# ss.net
KiCad netlist of a schematic drawn in EAGLE
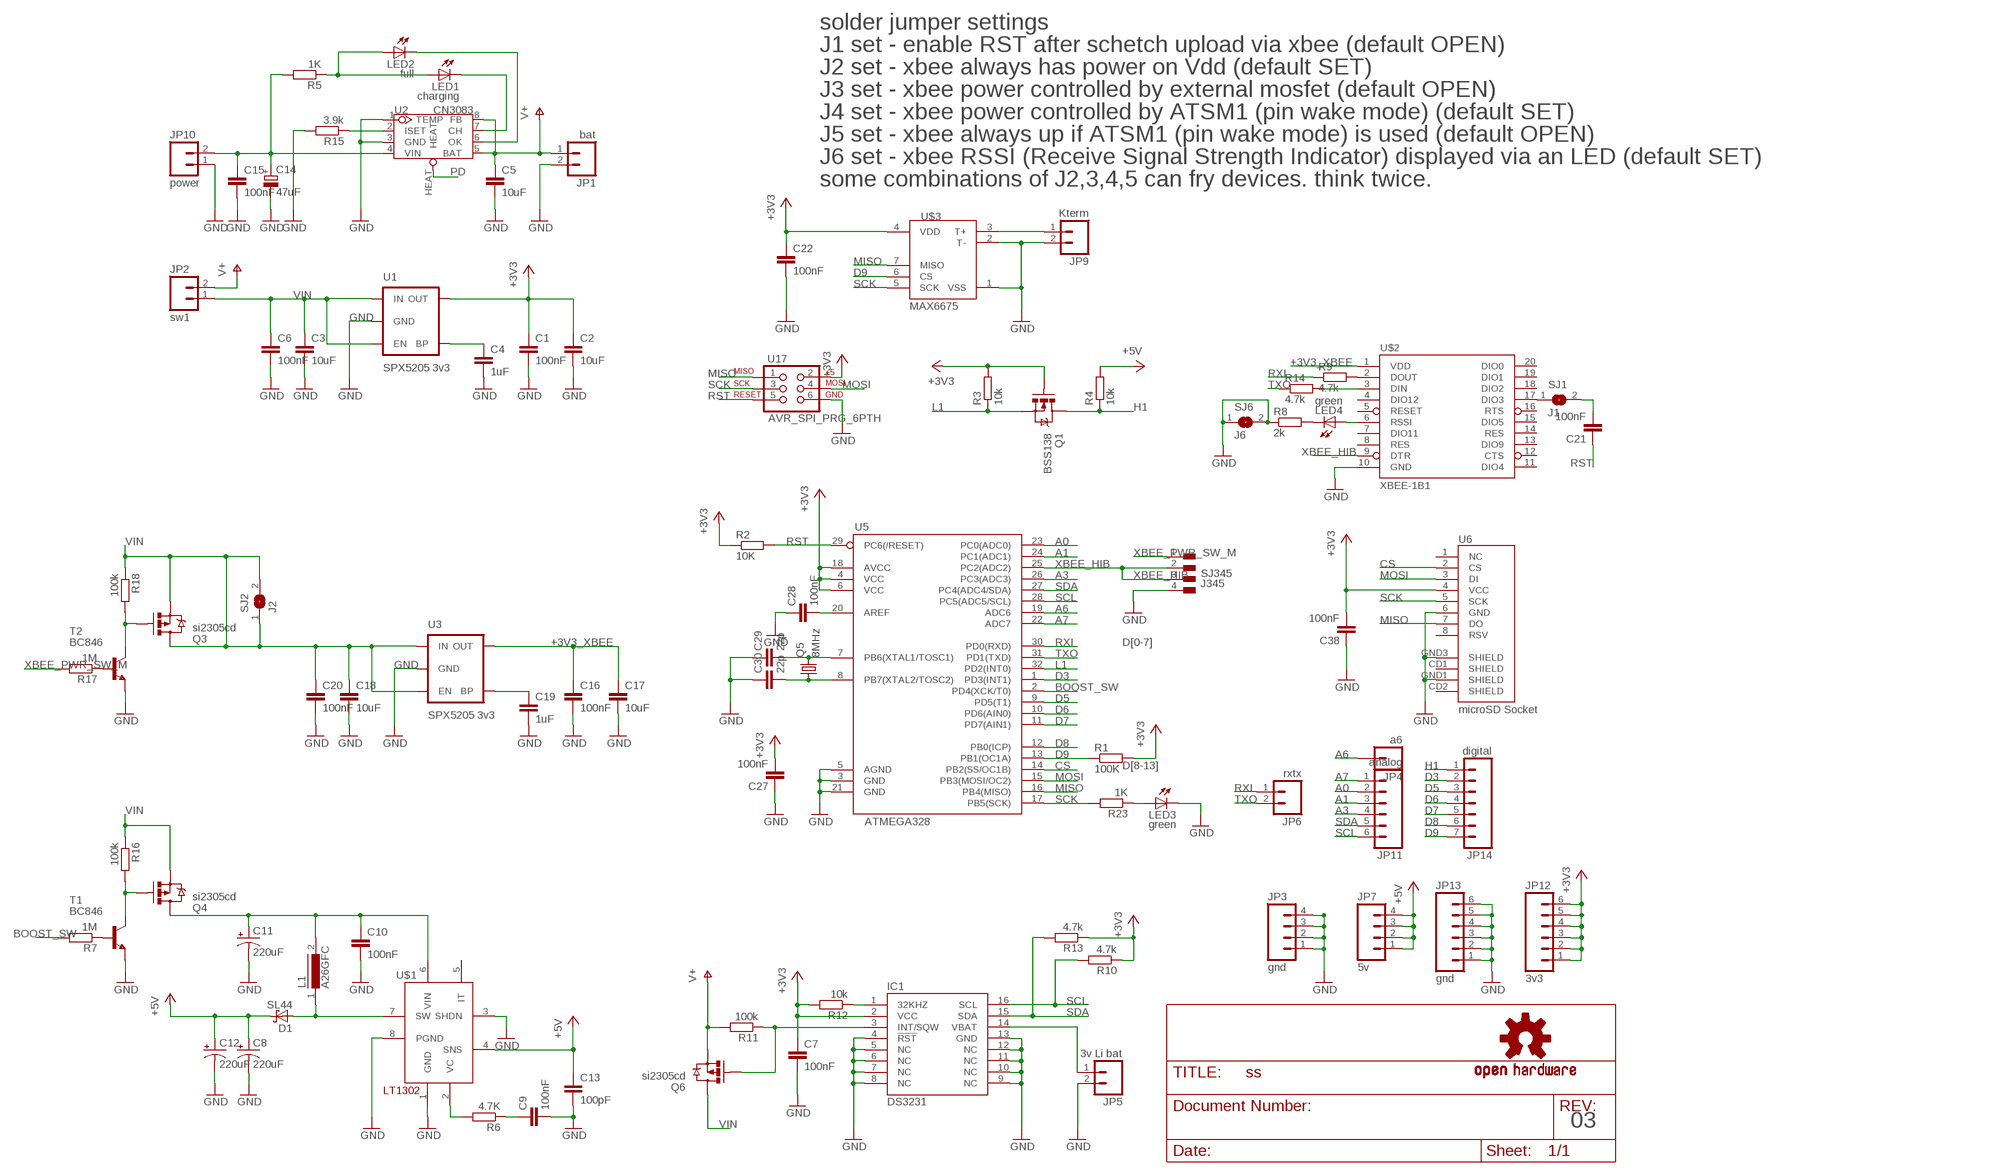
[diagram p0: schematic, sheet 1]

(export (version "E")
  (design (tool "Eeschema 10.0.6"))
  (components
    (comp (ref "C1")
      (value "100nF")
      (footprint "eagle-import:C0805")
      (libsource (lib "eagle-import") (part "C-EUC0805"))
    )
    (comp (ref "C2")
      (value "10uF")
      (footprint "eagle-import:C1206")
      (libsource (lib "eagle-import") (part "C-EUC1206"))
    )
    (comp (ref "C3")
      (value "10uF")
      (footprint "eagle-import:C1206")
      (libsource (lib "eagle-import") (part "C-EUC1206"))
    )
    (comp (ref "C4")
      (value "1uF")
      (footprint "eagle-import:C0805")
      (libsource (lib "eagle-import") (part "C-EUC0805"))
    )
    (comp (ref "C5")
      (value "10uF")
      (footprint "eagle-import:C1206")
      (libsource (lib "eagle-import") (part "C-EUC1206"))
    )
    (comp (ref "C6")
      (value "100nF")
      (footprint "eagle-import:C0805")
      (libsource (lib "eagle-import") (part "C-EUC0805"))
    )
    (comp (ref "C7")
      (value "100nF")
      (footprint "eagle-import:C0805")
      (libsource (lib "eagle-import") (part "C-EUC0805"))
    )
    (comp (ref "C8")
      (value "220uF")
      (footprint "eagle-import:PANASONIC_D")
      (libsource (lib "eagle-import") (part "CAP_POLD"))
    )
    (comp (ref "C9")
      (value "100nF")
      (footprint "eagle-import:C0805")
      (libsource (lib "eagle-import") (part "C-EUC0805"))
    )
    (comp (ref "C10")
      (value "100nF")
      (footprint "eagle-import:C0805")
      (libsource (lib "eagle-import") (part "C-EUC0805"))
    )
    (comp (ref "C11")
      (value "220uF")
      (footprint "eagle-import:PANASONIC_D")
      (libsource (lib "eagle-import") (part "CAP_POLD"))
    )
    (comp (ref "C12")
      (value "220uF")
      (footprint "eagle-import:PANASONIC_D")
      (libsource (lib "eagle-import") (part "CAP_POLD"))
    )
    (comp (ref "C13")
      (value "100pF")
      (footprint "eagle-import:C0805")
      (libsource (lib "eagle-import") (part "C-EUC0805"))
    )
    (comp (ref "C14")
      (value "47uF")
      (footprint "eagle-import:CT7343")
      (libsource (lib "eagle-import") (part "CPOL-EUCT7343"))
    )
    (comp (ref "C15")
      (value "100nF")
      (footprint "eagle-import:C0805")
      (libsource (lib "eagle-import") (part "C-EUC0805"))
    )
    (comp (ref "C16")
      (value "100nF")
      (footprint "eagle-import:C0805")
      (libsource (lib "eagle-import") (part "C-EUC0805"))
    )
    (comp (ref "C17")
      (value "10uF")
      (footprint "eagle-import:C1206")
      (libsource (lib "eagle-import") (part "C-EUC1206"))
    )
    (comp (ref "C18")
      (value "10uF")
      (footprint "eagle-import:C1206")
      (libsource (lib "eagle-import") (part "C-EUC1206"))
    )
    (comp (ref "C19")
      (value "1uF")
      (footprint "eagle-import:C0805")
      (libsource (lib "eagle-import") (part "C-EUC0805"))
    )
    (comp (ref "C20")
      (value "100nF")
      (footprint "eagle-import:C0805")
      (libsource (lib "eagle-import") (part "C-EUC0805"))
    )
    (comp (ref "C21")
      (value "100nF")
      (footprint "eagle-import:C0805")
      (libsource (lib "eagle-import") (part "C-EUC0805"))
    )
    (comp (ref "C22")
      (value "100nF")
      (footprint "eagle-import:C0805")
      (libsource (lib "eagle-import") (part "C-EUC0805"))
    )
    (comp (ref "C27")
      (value "100nF")
      (footprint "eagle-import:C0805")
      (libsource (lib "eagle-import") (part "C-EUC0805"))
    )
    (comp (ref "C28")
      (value "100nF")
      (footprint "eagle-import:C0805")
      (libsource (lib "eagle-import") (part "C-EUC0805"))
    )
    (comp (ref "C29")
      (value "22p")
      (footprint "eagle-import:C0805")
      (libsource (lib "eagle-import") (part "C-EUC0805"))
    )
    (comp (ref "C30")
      (value "22p")
      (footprint "eagle-import:C0805")
      (libsource (lib "eagle-import") (part "C-EUC0805"))
    )
    (comp (ref "C38")
      (value "100nF")
      (footprint "eagle-import:C0805")
      (libsource (lib "eagle-import") (part "C-EUC0805"))
    )
    (comp (ref "D1")
      (value "SL44")
      (footprint "eagle-import:SMC")
      (libsource (lib "eagle-import") (part "SCHOTTKY-DIODESMC"))
    )
    (comp (ref "IC1")
      (value "DS3231")
      (footprint "eagle-import:SO-16")
      (libsource (lib "eagle-import") (part "DS3231"))
    )
    (comp (ref "JP1")
      (value "bat")
      (footprint "eagle-import:1X02")
      (libsource (lib "eagle-import") (part "M02PTH"))
    )
    (comp (ref "JP2")
      (value "sw1")
      (footprint "eagle-import:1X02")
      (libsource (lib "eagle-import") (part "M02PTH"))
    )
    (comp (ref "JP3")
      (value "gnd")
      (footprint "eagle-import:1X04")
      (libsource (lib "eagle-import") (part "M04PTH"))
    )
    (comp (ref "JP4")
      (value "a6")
      (footprint "eagle-import:1X01")
      (libsource (lib "eagle-import") (part "M01PTH"))
    )
    (comp (ref "JP5")
      (value "3v Li bat")
      (footprint "eagle-import:1X02")
      (libsource (lib "eagle-import") (part "M02PTH"))
    )
    (comp (ref "JP6")
      (value "rxtx")
      (footprint "eagle-import:1X02")
      (libsource (lib "eagle-import") (part "M02PTH"))
    )
    (comp (ref "JP7")
      (value "5v")
      (footprint "eagle-import:1X04")
      (libsource (lib "eagle-import") (part "M04PTH"))
    )
    (comp (ref "JP9")
      (value "Kterm")
      (footprint "eagle-import:1X02")
      (libsource (lib "eagle-import") (part "M02PTH"))
    )
    (comp (ref "JP10")
      (value "power")
      (footprint "eagle-import:1X02")
      (libsource (lib "eagle-import") (part "M02PTH"))
    )
    (comp (ref "JP11")
      (value "analog")
      (footprint "eagle-import:1X06")
      (libsource (lib "eagle-import") (part "M06SIP"))
    )
    (comp (ref "JP12")
      (value "3v3")
      (footprint "eagle-import:1X06")
      (libsource (lib "eagle-import") (part "M06SIP"))
    )
    (comp (ref "JP13")
      (value "gnd")
      (footprint "eagle-import:1X06")
      (libsource (lib "eagle-import") (part "M06SIP"))
    )
    (comp (ref "JP14")
      (value "digital")
      (footprint "eagle-import:1X07")
      (libsource (lib "eagle-import") (part "M07"))
    )
    (comp (ref "L1")
      (value "A26GFC")
      (footprint "eagle-import:A26GFC")
      (libsource (lib "eagle-import") (part "A26GFC"))
    )
    (comp (ref "LED1")
      (value "charging")
      (footprint "eagle-import:CHIP-LED0805")
      (libsource (lib "eagle-import") (part "LEDCHIP-LED0805"))
    )
    (comp (ref "LED2")
      (value "full")
      (footprint "eagle-import:CHIP-LED0805")
      (libsource (lib "eagle-import") (part "LEDCHIP-LED0805"))
    )
    (comp (ref "LED3")
      (value "green")
      (footprint "eagle-import:CHIP-LED0805")
      (libsource (lib "eagle-import") (part "LEDCHIP-LED0805"))
    )
    (comp (ref "LED4")
      (value "green")
      (footprint "eagle-import:CHIP-LED0805")
      (libsource (lib "eagle-import") (part "LEDCHIP-LED0805"))
    )
    (comp (ref "Q1")
      (value "BSS138")
      (footprint "eagle-import:SOT23-3")
      (libsource (lib "eagle-import") (part "MOSFET-NCHANNELSMD"))
    )
    (comp (ref "Q3")
      (value "si2305cd")
      (footprint "eagle-import:SOT23-3_POWER")
      (libsource (lib "eagle-import") (part "MOSFET-PCHANNELSMD_POWER"))
    )
    (comp (ref "Q4")
      (value "si2305cd")
      (footprint "eagle-import:SOT23-3_POWER")
      (libsource (lib "eagle-import") (part "MOSFET-PCHANNELSMD_POWER"))
    )
    (comp (ref "Q5")
      (value "8MHz")
      (footprint "eagle-import:CRYSTAL_5X3.2")
      (libsource (lib "eagle-import") (part "CRYTAL"))
    )
    (comp (ref "Q6")
      (value "si2305cd")
      (footprint "eagle-import:SOT23-3_POWER")
      (libsource (lib "eagle-import") (part "MOSFET-PCHANNELSMD_POWER"))
    )
    (comp (ref "R1")
      (value "100K")
      (footprint "eagle-import:R0805W")
      (libsource (lib "eagle-import") (part "R-EU_R0805W"))
    )
    (comp (ref "R2")
      (value "10K")
      (footprint "eagle-import:R0805W")
      (libsource (lib "eagle-import") (part "R-EU_R0805W"))
    )
    (comp (ref "R3")
      (value "10k")
      (footprint "eagle-import:R0805W")
      (libsource (lib "eagle-import") (part "R-EU_R0805W"))
    )
    (comp (ref "R4")
      (value "10k")
      (footprint "eagle-import:R0805W")
      (libsource (lib "eagle-import") (part "R-EU_R0805W"))
    )
    (comp (ref "R5")
      (value "1K")
      (footprint "eagle-import:R0805W")
      (libsource (lib "eagle-import") (part "R-EU_R0805W"))
    )
    (comp (ref "R6")
      (value "4.7K")
      (footprint "eagle-import:R0805W")
      (libsource (lib "eagle-import") (part "R-EU_R0805W"))
    )
    (comp (ref "R7")
      (value "1M")
      (footprint "eagle-import:R0805W")
      (libsource (lib "eagle-import") (part "R-EU_R0805W"))
    )
    (comp (ref "R8")
      (value "2k")
      (footprint "eagle-import:R0805W")
      (libsource (lib "eagle-import") (part "R-EU_R0805W"))
    )
    (comp (ref "R9")
      (value "4.7k")
      (footprint "eagle-import:R0805W")
      (libsource (lib "eagle-import") (part "R-EU_R0805W"))
    )
    (comp (ref "R10")
      (value "4.7k")
      (footprint "eagle-import:R0805W")
      (libsource (lib "eagle-import") (part "R-EU_R0805W"))
    )
    (comp (ref "R11")
      (value "100k")
      (footprint "eagle-import:R0805W")
      (libsource (lib "eagle-import") (part "R-EU_R0805W"))
    )
    (comp (ref "R12")
      (value "10k")
      (footprint "eagle-import:R0805W")
      (libsource (lib "eagle-import") (part "R-EU_R0805W"))
    )
    (comp (ref "R13")
      (value "4.7k")
      (footprint "eagle-import:R0805W")
      (libsource (lib "eagle-import") (part "R-EU_R0805W"))
    )
    (comp (ref "R14")
      (value "4.7k")
      (footprint "eagle-import:R0805W")
      (libsource (lib "eagle-import") (part "R-EU_R0805W"))
    )
    (comp (ref "R15")
      (value "3.9k")
      (footprint "eagle-import:R0805W")
      (libsource (lib "eagle-import") (part "R-EU_R0805W"))
    )
    (comp (ref "R16")
      (value "100k")
      (footprint "eagle-import:R0805W")
      (libsource (lib "eagle-import") (part "R-EU_R0805W"))
    )
    (comp (ref "R17")
      (value "1M")
      (footprint "eagle-import:R0805W")
      (libsource (lib "eagle-import") (part "R-EU_R0805W"))
    )
    (comp (ref "R18")
      (value "100k")
      (footprint "eagle-import:R0805W")
      (libsource (lib "eagle-import") (part "R-EU_R0805W"))
    )
    (comp (ref "R23")
      (value "1K")
      (footprint "eagle-import:R0805W")
      (libsource (lib "eagle-import") (part "R-EU_R0805W"))
    )
    (comp (ref "SJ1") (value "J1") (footprint "eagle-import:SJ") (libsource (lib "eagle-import") (part "SJ")))
    (comp (ref "SJ2") (value "J2") (footprint "eagle-import:SJ") (libsource (lib "eagle-import") (part "SJ")))
    (comp (ref "SJ6") (value "J6") (footprint "eagle-import:SJ") (libsource (lib "eagle-import") (part "SJ")))
    (comp (ref "SJ345")
      (value "J345")
      (footprint "eagle-import:SJ_4P")
      (libsource (lib "eagle-import") (part "SJ_4P"))
    )
    (comp (ref "T1")
      (value "BC846")
      (footprint "eagle-import:SOT23")
      (libsource (lib "eagle-import") (part "BC846"))
    )
    (comp (ref "T2")
      (value "BC846")
      (footprint "eagle-import:SOT23")
      (libsource (lib "eagle-import") (part "BC846"))
    )
    (comp (ref "U$1")
      (value "LT1302SOIC8")
      (footprint "eagle-import:SO08")
      (libsource (lib "eagle-import") (part "LT1302SOIC8"))
    )
    (comp (ref "U$2")
      (value "XBEE-1B1")
      (footprint "eagle-import:XBEE-1")
      (libsource (lib "eagle-import") (part "XBEE-1B1"))
    )
    (comp (ref "U$3")
      (value "MAX6675")
      (footprint "eagle-import:SO08-MAX6675")
      (libsource (lib "eagle-import") (part "MAX6675"))
    )
    (comp (ref "U$7")
      (value "OSHW-LOGOM")
      (footprint "eagle-import:OSHW-LOGO-M")
      (libsource (lib "eagle-import") (part "OSHW-LOGOM"))
    )
    (comp (ref "U1")
      (value "SPX5205 3v3")
      (footprint "eagle-import:SOT23-5")
      (libsource (lib "eagle-import") (part "V_REG_LDOSMD"))
    )
    (comp (ref "U2")
      (value "CN3083")
      (footprint "eagle-import:SOP8-W_-HEAT")
      (libsource (lib "eagle-import") (part "CN3083"))
    )
    (comp (ref "U3")
      (value "SPX5205 3v3")
      (footprint "eagle-import:SOT23-5")
      (libsource (lib "eagle-import") (part "V_REG_LDOSMD"))
    )
    (comp (ref "U5")
      (value "ATMEGA328")
      (footprint "eagle-import:TQFP32-08")
      (libsource (lib "eagle-import") (part "ATMEGA168"))
    )
    (comp (ref "U6")
      (value "microSD Socket")
      (footprint "eagle-import:MICRO-SD-SOCKET-PP")
      (libsource (lib "eagle-import") (part "USD-SOCKETNEW"))
    )
    (comp (ref "U17")
      (value "AVR_SPI_PRG_6PTH")
      (footprint "eagle-import:2X3")
      (libsource (lib "eagle-import") (part "AVR_SPI_PRG_6PTH"))
    )
  )
  (nets
    (net (code "1") (name "+3V3") (class "Default")
      (node (ref "C1") (pin "1") (pinfunction "1_1") (pintype "passive"))
      (node (ref "C2") (pin "1") (pinfunction "1_1") (pintype "passive"))
      (node (ref "C22") (pin "1") (pinfunction "1_1") (pintype "passive"))
      (node (ref "C27") (pin "2") (pinfunction "2_2") (pintype "passive"))
      (node (ref "C38") (pin "2") (pinfunction "2_2") (pintype "passive"))
      (node (ref "C7") (pin "1") (pinfunction "1_1") (pintype "passive"))
      (node (ref "IC1") (pin "2") (pinfunction "VCC_2") (pintype "power_in"))
      (node (ref "JP12") (pin "1") (pinfunction "1_1") (pintype "passive"))
      (node (ref "JP12") (pin "2") (pinfunction "2_2") (pintype "passive"))
      (node (ref "JP12") (pin "3") (pinfunction "3_3") (pintype "passive"))
      (node (ref "JP12") (pin "4") (pinfunction "4_4") (pintype "passive"))
      (node (ref "JP12") (pin "5") (pinfunction "5_5") (pintype "passive"))
      (node (ref "JP12") (pin "6") (pinfunction "6_6") (pintype "passive"))
      (node (ref "Q1") (pin "1") (pinfunction "G_1") (pintype "passive"))
      (node (ref "R1") (pin "2") (pinfunction "2_2") (pintype "passive"))
      (node (ref "R10") (pin "1") (pinfunction "1_1") (pintype "passive"))
      (node (ref "R12") (pin "2") (pinfunction "2_2") (pintype "passive"))
      (node (ref "R13") (pin "1") (pinfunction "1_1") (pintype "passive"))
      (node (ref "R2") (pin "1") (pinfunction "1_1") (pintype "passive"))
      (node (ref "R3") (pin "2") (pinfunction "2_2") (pintype "passive"))
      (node (ref "U$3") (pin "4") (pinfunction "VDD_4") (pintype "bidirectional"))
      (node (ref "U1") (pin "5") (pinfunction "OUT_5") (pintype "passive"))
      (node (ref "U17") (pin "2") (pinfunction "2_2") (pintype "passive"))
      (node (ref "U5") (pin "18") (pinfunction "AVCC_18") (pintype "bidirectional"))
      (node (ref "U5") (pin "4") (pinfunction "VCC_4") (pintype "bidirectional"))
      (node (ref "U5") (pin "6") (pinfunction "VCC_6") (pintype "bidirectional"))
      (node (ref "U6") (pin "4") (pinfunction "VCC_4") (pintype "bidirectional"))
    )
    (net (code "2") (name "+5V") (class "Default")
      (node (ref "C12") (pin "+") (pinfunction "+_+") (pintype "passive"))
      (node (ref "C13") (pin "1") (pinfunction "1_1") (pintype "passive"))
      (node (ref "C8") (pin "+") (pinfunction "+_+") (pintype "passive"))
      (node (ref "D1") (pin "C") (pinfunction "C_C") (pintype "passive"))
      (node (ref "JP7") (pin "1") (pinfunction "1_1") (pintype "passive"))
      (node (ref "JP7") (pin "2") (pinfunction "2_2") (pintype "passive"))
      (node (ref "JP7") (pin "3") (pinfunction "3_3") (pintype "passive"))
      (node (ref "JP7") (pin "4") (pinfunction "4_4") (pintype "passive"))
      (node (ref "R4") (pin "2") (pinfunction "2_2") (pintype "passive"))
      (node (ref "U$1") (pin "4") (pinfunction "SNS_4") (pintype "passive"))
    )
    (net (code "3") (name "/+3V3_XBEE") (class "Default")
      (node (ref "C16") (pin "1") (pinfunction "1_1") (pintype "passive"))
      (node (ref "C17") (pin "1") (pinfunction "1_1") (pintype "passive"))
      (node (ref "U$2") (pin "1") (pinfunction "VDD_1") (pintype "power_in"))
      (node (ref "U3") (pin "5") (pinfunction "OUT_5") (pintype "passive"))
    )
    (net (code "4") (name "/A0") (class "Default")
      (node (ref "JP11") (pin "2") (pinfunction "2_2") (pintype "passive"))
      (node (ref "U5") (pin "23") (pinfunction "PC0(ADC0)_23") (pintype "bidirectional"))
    )
    (net (code "5") (name "/A1") (class "Default")
      (node (ref "JP11") (pin "3") (pinfunction "3_3") (pintype "passive"))
      (node (ref "U5") (pin "24") (pinfunction "PC1(ADC1)_24") (pintype "bidirectional"))
    )
    (net (code "6") (name "/A3") (class "Default")
      (node (ref "JP11") (pin "4") (pinfunction "4_4") (pintype "passive"))
      (node (ref "U5") (pin "26") (pinfunction "PC3(ADC3)_26") (pintype "bidirectional"))
    )
    (net (code "7") (name "/A6") (class "Default")
      (node (ref "JP4") (pin "1") (pinfunction "1_1") (pintype "passive"))
      (node (ref "U5") (pin "19") (pinfunction "ADC6_19") (pintype "bidirectional"))
    )
    (net (code "8") (name "/A7") (class "Default")
      (node (ref "JP11") (pin "1") (pinfunction "1_1") (pintype "passive"))
      (node (ref "U5") (pin "22") (pinfunction "ADC7_22") (pintype "bidirectional"))
    )
    (net (code "9") (name "/BOOST_SW") (class "Default")
      (node (ref "R7") (pin "2") (pinfunction "2_2") (pintype "passive"))
      (node (ref "U5") (pin "2") (pinfunction "PD4(XCK/T0)_2") (pintype "bidirectional"))
    )
    (net (code "10") (name "/CS") (class "Default")
      (node (ref "U5") (pin "14") (pinfunction "PB2(SS/OC1B)_14") (pintype "bidirectional"))
      (node (ref "U6") (pin "2") (pinfunction "CS_2") (pintype "bidirectional"))
    )
    (net (code "11") (name "/D3") (class "Default")
      (node (ref "JP14") (pin "2") (pinfunction "2_2") (pintype "passive"))
      (node (ref "U5") (pin "1") (pinfunction "PD3(INT1)_1") (pintype "bidirectional"))
    )
    (net (code "12") (name "/D5") (class "Default")
      (node (ref "JP14") (pin "3") (pinfunction "3_3") (pintype "passive"))
      (node (ref "U5") (pin "9") (pinfunction "PD5(T1)_9") (pintype "bidirectional"))
    )
    (net (code "13") (name "/D6") (class "Default")
      (node (ref "JP14") (pin "4") (pinfunction "4_4") (pintype "passive"))
      (node (ref "U5") (pin "10") (pinfunction "PD6(AIN0)_10") (pintype "bidirectional"))
    )
    (net (code "14") (name "/D7") (class "Default")
      (node (ref "JP14") (pin "5") (pinfunction "5_5") (pintype "passive"))
      (node (ref "U5") (pin "11") (pinfunction "PD7(AIN1)_11") (pintype "bidirectional"))
    )
    (net (code "15") (name "/D8") (class "Default")
      (node (ref "JP14") (pin "6") (pinfunction "6_6") (pintype "passive"))
      (node (ref "U5") (pin "12") (pinfunction "PB0(ICP)_12") (pintype "bidirectional"))
    )
    (net (code "16") (name "/D9") (class "Default")
      (node (ref "JP14") (pin "7") (pinfunction "7_7") (pintype "passive"))
      (node (ref "R1") (pin "1") (pinfunction "1_1") (pintype "passive"))
      (node (ref "U$3") (pin "6") (pinfunction "CS_6") (pintype "bidirectional"))
      (node (ref "U5") (pin "13") (pinfunction "PB1(OC1A)_13") (pintype "bidirectional"))
    )
    (net (code "17") (name "/H1") (class "Default")
      (node (ref "JP14") (pin "1") (pinfunction "1_1") (pintype "passive"))
      (node (ref "Q1") (pin "3") (pinfunction "D_3") (pintype "passive"))
      (node (ref "R4") (pin "1") (pinfunction "1_1") (pintype "passive"))
    )
    (net (code "18") (name "/L1") (class "Default")
      (node (ref "Q1") (pin "2") (pinfunction "S_2") (pintype "passive"))
      (node (ref "R3") (pin "1") (pinfunction "1_1") (pintype "passive"))
      (node (ref "U5") (pin "32") (pinfunction "PD2(INT0)_32") (pintype "bidirectional"))
    )
    (net (code "19") (name "/MISO") (class "Default")
      (node (ref "U$3") (pin "7") (pinfunction "MISO_7") (pintype "bidirectional"))
      (node (ref "U17") (pin "1") (pinfunction "1_1") (pintype "passive"))
      (node (ref "U5") (pin "16") (pinfunction "PB4(MISO)_16") (pintype "bidirectional"))
      (node (ref "U6") (pin "7") (pinfunction "DO_7") (pintype "bidirectional"))
    )
    (net (code "20") (name "/MOSI") (class "Default")
      (node (ref "U17") (pin "4") (pinfunction "4_4") (pintype "passive"))
      (node (ref "U5") (pin "15") (pinfunction "PB3(MOSI/OC2)_15") (pintype "bidirectional"))
      (node (ref "U6") (pin "3") (pinfunction "DI_3") (pintype "bidirectional"))
    )
    (net (code "21") (name "/PD") (class "Default")
      (node (ref "U2") (pin "HEAT") (pinfunction "HEAT_HEAT") (pintype "bidirectional"))
    )
    (net (code "22") (name "/RST") (class "Default")
      (node (ref "C21") (pin "1") (pinfunction "1_1") (pintype "passive"))
      (node (ref "R2") (pin "2") (pinfunction "2_2") (pintype "passive"))
      (node (ref "U17") (pin "5") (pinfunction "5_5") (pintype "passive"))
      (node (ref "U5") (pin "29") (pinfunction "PC6(/RESET)_29") (pintype "bidirectional"))
    )
    (net (code "23") (name "/RXI") (class "Default")
      (node (ref "JP6") (pin "1") (pinfunction "1_1") (pintype "passive"))
      (node (ref "R9") (pin "1") (pinfunction "1_1") (pintype "passive"))
      (node (ref "U5") (pin "30") (pinfunction "PD0(RXD)_30") (pintype "bidirectional"))
    )
    (net (code "24") (name "/SCK") (class "Default")
      (node (ref "R23") (pin "2") (pinfunction "2_2") (pintype "passive"))
      (node (ref "U$3") (pin "5") (pinfunction "SCK_5") (pintype "bidirectional"))
      (node (ref "U17") (pin "3") (pinfunction "3_3") (pintype "passive"))
      (node (ref "U5") (pin "17") (pinfunction "PB5(SCK)_17") (pintype "bidirectional"))
      (node (ref "U6") (pin "5") (pinfunction "SCK_5") (pintype "bidirectional"))
    )
    (net (code "25") (name "/SCL") (class "Default")
      (node (ref "IC1") (pin "16") (pinfunction "SCL_16") (pintype "bidirectional"))
      (node (ref "JP11") (pin "6") (pinfunction "6_6") (pintype "passive"))
      (node (ref "R10") (pin "2") (pinfunction "2_2") (pintype "passive"))
      (node (ref "U5") (pin "28") (pinfunction "PC5(ADC5/SCL)_28") (pintype "bidirectional"))
    )
    (net (code "26") (name "/SDA") (class "Default")
      (node (ref "IC1") (pin "15") (pinfunction "SDA_15") (pintype "bidirectional"))
      (node (ref "JP11") (pin "5") (pinfunction "5_5") (pintype "passive"))
      (node (ref "R13") (pin "2") (pinfunction "2_2") (pintype "passive"))
      (node (ref "U5") (pin "27") (pinfunction "PC4(ADC4/SDA)_27") (pintype "bidirectional"))
    )
    (net (code "27") (name "/TXO") (class "Default")
      (node (ref "JP6") (pin "2") (pinfunction "2_2") (pintype "passive"))
      (node (ref "R14") (pin "1") (pinfunction "1_1") (pintype "passive"))
      (node (ref "U5") (pin "31") (pinfunction "PD1(TXD)_31") (pintype "bidirectional"))
    )
    (net (code "28") (name "/VIN") (class "Default")
      (node (ref "C18") (pin "1") (pinfunction "1_1") (pintype "passive"))
      (node (ref "C20") (pin "1") (pinfunction "1_1") (pintype "passive"))
      (node (ref "C3") (pin "1") (pinfunction "1_1") (pintype "passive"))
      (node (ref "C6") (pin "1") (pinfunction "1_1") (pintype "passive"))
      (node (ref "JP2") (pin "1") (pinfunction "1_1") (pintype "passive"))
      (node (ref "Q3") (pin "2") (pinfunction "S_2") (pintype "passive"))
      (node (ref "Q3") (pin "3") (pinfunction "D_3") (pintype "passive"))
      (node (ref "Q4") (pin "2") (pinfunction "S_2") (pintype "passive"))
      (node (ref "Q6") (pin "3") (pinfunction "D_3") (pintype "passive"))
      (node (ref "R16") (pin "1") (pinfunction "1_1") (pintype "passive"))
      (node (ref "R18") (pin "1") (pinfunction "1_1") (pintype "passive"))
      (node (ref "SJ2") (pin "1") (pinfunction "1_1") (pintype "passive"))
      (node (ref "SJ2") (pin "2") (pinfunction "2_2") (pintype "passive"))
      (node (ref "U1") (pin "1") (pinfunction "IN_1") (pintype "input"))
      (node (ref "U1") (pin "3") (pinfunction "EN_3") (pintype "input"))
      (node (ref "U3") (pin "1") (pinfunction "IN_1") (pintype "input"))
      (node (ref "U3") (pin "3") (pinfunction "EN_3") (pintype "input"))
    )
    (net (code "29") (name "/XBEE_HIB") (class "Default")
      (node (ref "SJ345") (pin "2") (pinfunction "2_2") (pintype "passive"))
      (node (ref "SJ345") (pin "3") (pinfunction "3_3") (pintype "passive"))
      (node (ref "U$2") (pin "9") (pinfunction "DTR_9") (pintype "bidirectional"))
      (node (ref "U5") (pin "25") (pinfunction "PC2(ADC2)_25") (pintype "bidirectional"))
    )
    (net (code "30") (name "/XBEE_PWR_SW_M") (class "Default")
      (node (ref "R17") (pin "2") (pinfunction "2_2") (pintype "passive"))
      (node (ref "SJ345") (pin "1") (pinfunction "1_1") (pintype "passive"))
    )
    (net (code "31") (name "GND") (class "Default")
      (node (ref "C1") (pin "2") (pinfunction "2_2") (pintype "passive"))
      (node (ref "C10") (pin "2") (pinfunction "2_2") (pintype "passive"))
      (node (ref "C11") (pin "-") (pinfunction "-_-") (pintype "passive"))
      (node (ref "C12") (pin "-") (pinfunction "-_-") (pintype "passive"))
      (node (ref "C13") (pin "2") (pinfunction "2_2") (pintype "passive"))
      (node (ref "C14") (pin "-") (pinfunction "-_-") (pintype "passive"))
      (node (ref "C15") (pin "2") (pinfunction "2_2") (pintype "passive"))
      (node (ref "C16") (pin "2") (pinfunction "2_2") (pintype "passive"))
      (node (ref "C17") (pin "2") (pinfunction "2_2") (pintype "passive"))
      (node (ref "C18") (pin "2") (pinfunction "2_2") (pintype "passive"))
      (node (ref "C19") (pin "2") (pinfunction "2_2") (pintype "passive"))
      (node (ref "C2") (pin "2") (pinfunction "2_2") (pintype "passive"))
      (node (ref "C20") (pin "2") (pinfunction "2_2") (pintype "passive"))
      (node (ref "C22") (pin "2") (pinfunction "2_2") (pintype "passive"))
      (node (ref "C27") (pin "1") (pinfunction "1_1") (pintype "passive"))
      (node (ref "C28") (pin "1") (pinfunction "1_1") (pintype "passive"))
      (node (ref "C29") (pin "1") (pinfunction "1_1") (pintype "passive"))
      (node (ref "C3") (pin "2") (pinfunction "2_2") (pintype "passive"))
      (node (ref "C30") (pin "1") (pinfunction "1_1") (pintype "passive"))
      (node (ref "C38") (pin "1") (pinfunction "1_1") (pintype "passive"))
      (node (ref "C4") (pin "2") (pinfunction "2_2") (pintype "passive"))
      (node (ref "C5") (pin "2") (pinfunction "2_2") (pintype "passive"))
      (node (ref "C6") (pin "2") (pinfunction "2_2") (pintype "passive"))
      (node (ref "C7") (pin "2") (pinfunction "2_2") (pintype "passive"))
      (node (ref "C8") (pin "-") (pinfunction "-_-") (pintype "passive"))
      (node (ref "C9") (pin "2") (pinfunction "2_2") (pintype "passive"))
      (node (ref "IC1") (pin "10") (pinfunction "NC_10") (pintype "bidirectional"))
      (node (ref "IC1") (pin "11") (pinfunction "NC_11") (pintype "bidirectional"))
      (node (ref "IC1") (pin "12") (pinfunction "NC_12") (pintype "bidirectional"))
      (node (ref "IC1") (pin "13") (pinfunction "GND_13") (pintype "power_in"))
      (node (ref "IC1") (pin "4") (pinfunction "~{RST}_4") (pintype "bidirectional"))
      (node (ref "IC1") (pin "5") (pinfunction "NC_5") (pintype "bidirectional"))
      (node (ref "IC1") (pin "6") (pinfunction "NC_6") (pintype "bidirectional"))
      (node (ref "IC1") (pin "7") (pinfunction "NC_7") (pintype "bidirectional"))
      (node (ref "IC1") (pin "8") (pinfunction "NC_8") (pintype "bidirectional"))
      (node (ref "IC1") (pin "9") (pinfunction "NC_9") (pintype "bidirectional"))
      (node (ref "JP1") (pin "2") (pinfunction "2_2") (pintype "passive"))
      (node (ref "JP10") (pin "1") (pinfunction "1_1") (pintype "passive"))
      (node (ref "JP13") (pin "1") (pinfunction "1_1") (pintype "passive"))
      (node (ref "JP13") (pin "2") (pinfunction "2_2") (pintype "passive"))
      (node (ref "JP13") (pin "3") (pinfunction "3_3") (pintype "passive"))
      (node (ref "JP13") (pin "4") (pinfunction "4_4") (pintype "passive"))
      (node (ref "JP13") (pin "5") (pinfunction "5_5") (pintype "passive"))
      (node (ref "JP13") (pin "6") (pinfunction "6_6") (pintype "passive"))
      (node (ref "JP3") (pin "1") (pinfunction "1_1") (pintype "passive"))
      (node (ref "JP3") (pin "2") (pinfunction "2_2") (pintype "passive"))
      (node (ref "JP3") (pin "3") (pinfunction "3_3") (pintype "passive"))
      (node (ref "JP3") (pin "4") (pinfunction "4_4") (pintype "passive"))
      (node (ref "JP5") (pin "2") (pinfunction "2_2") (pintype "passive"))
      (node (ref "JP9") (pin "2") (pinfunction "2_2") (pintype "passive"))
      (node (ref "LED3") (pin "C") (pinfunction "C_C") (pintype "passive"))
      (node (ref "R15") (pin "2") (pinfunction "2_2") (pintype "passive"))
      (node (ref "R8") (pin "1") (pinfunction "1_1") (pintype "passive"))
      (node (ref "SJ345") (pin "4") (pinfunction "4_4") (pintype "passive"))
      (node (ref "SJ6") (pin "1") (pinfunction "1_1") (pintype "passive"))
      (node (ref "SJ6") (pin "2") (pinfunction "2_2") (pintype "passive"))
      (node (ref "T1") (pin "2") (pinfunction "E_2") (pintype "passive"))
      (node (ref "T2") (pin "2") (pinfunction "E_2") (pintype "passive"))
      (node (ref "U$1") (pin "1") (pinfunction "GND_1") (pintype "input"))
      (node (ref "U$1") (pin "3") (pinfunction "SHDN_3") (pintype "input"))
      (node (ref "U$1") (pin "8") (pinfunction "PGND_8") (pintype "input"))
      (node (ref "U$2") (pin "10") (pinfunction "GND_10") (pintype "power_in"))
      (node (ref "U$3") (pin "1") (pinfunction "VSS_1") (pintype "bidirectional"))
      (node (ref "U$3") (pin "2") (pinfunction "T-_2") (pintype "bidirectional"))
      (node (ref "U1") (pin "2") (pinfunction "GND_2") (pintype "input"))
      (node (ref "U17") (pin "6") (pinfunction "6_6") (pintype "passive"))
      (node (ref "U2") (pin "1") (pinfunction "TEMP_1") (pintype "bidirectional"))
      (node (ref "U2") (pin "3") (pinfunction "GND_3") (pintype "bidirectional"))
      (node (ref "U3") (pin "2") (pinfunction "GND_2") (pintype "input"))
      (node (ref "U5") (pin "21") (pinfunction "GND_21") (pintype "bidirectional"))
      (node (ref "U5") (pin "3") (pinfunction "GND_3") (pintype "bidirectional"))
      (node (ref "U5") (pin "5") (pinfunction "AGND_5") (pintype "bidirectional"))
      (node (ref "U6") (pin "6") (pinfunction "GND_6") (pintype "bidirectional"))
      (node (ref "U6") (pin "GND1") (pinfunction "SHIELD_GND1") (pintype "bidirectional"))
      (node (ref "U6") (pin "GND3") (pinfunction "SHIELD_GND3") (pintype "bidirectional"))
    )
    (net (code "32") (name "Net-(C9-Pad1)") (class "Default")
      (node (ref "C9") (pin "1") (pinfunction "1_1") (pintype "passive"))
      (node (ref "R6") (pin "1") (pinfunction "1_1") (pintype "passive"))
    )
    (net (code "33") (name "Net-(C21-Pad2)") (class "Default")
      (node (ref "C21") (pin "2") (pinfunction "2_2") (pintype "passive"))
      (node (ref "SJ1") (pin "2") (pinfunction "2_2") (pintype "passive"))
    )
    (net (code "34") (name "Net-(IC1-32KHZ)") (class "Default")
      (node (ref "IC1") (pin "1") (pinfunction "32KHZ_1") (pintype "bidirectional"))
      (node (ref "R12") (pin "1") (pinfunction "1_1") (pintype "passive"))
    )
    (net (code "35") (name "Net-(IC1-INT{slash}SQW)") (class "Default")
      (node (ref "IC1") (pin "3") (pinfunction "INT/SQW_3") (pintype "bidirectional"))
      (node (ref "Q6") (pin "1") (pinfunction "G_1") (pintype "passive"))
      (node (ref "R11") (pin "1") (pinfunction "1_1") (pintype "passive"))
    )
    (net (code "36") (name "Net-(IC1-VBAT)") (class "Default")
      (node (ref "IC1") (pin "14") (pinfunction "VBAT_14") (pintype "bidirectional"))
      (node (ref "JP5") (pin "1") (pinfunction "1_1") (pintype "passive"))
    )
    (net (code "37") (name "Net-(LED1-PadA)") (class "Default")
      (node (ref "LED1") (pin "A") (pinfunction "A_A") (pintype "passive"))
      (node (ref "LED2") (pin "A") (pinfunction "A_A") (pintype "passive"))
      (node (ref "R5") (pin "1") (pinfunction "1_1") (pintype "passive"))
    )
    (net (code "38") (name "Net-(LED3-PadA)") (class "Default")
      (node (ref "LED3") (pin "A") (pinfunction "A_A") (pintype "passive"))
      (node (ref "R23") (pin "1") (pinfunction "1_1") (pintype "passive"))
    )
    (net (code "39") (name "Net-(LED4-PadC)") (class "Default")
      (node (ref "LED4") (pin "C") (pinfunction "C_C") (pintype "passive"))
      (node (ref "R8") (pin "2") (pinfunction "2_2") (pintype "passive"))
    )
    (net (code "40") (name "Net-(Q3-G)") (class "Default")
      (node (ref "Q3") (pin "1") (pinfunction "G_1") (pintype "passive"))
      (node (ref "R18") (pin "2") (pinfunction "2_2") (pintype "passive"))
      (node (ref "T2") (pin "3") (pinfunction "C_3") (pintype "passive"))
    )
    (net (code "41") (name "Net-(Q4-D)") (class "Default")
      (node (ref "C10") (pin "1") (pinfunction "1_1") (pintype "passive"))
      (node (ref "C11") (pin "+") (pinfunction "+_+") (pintype "passive"))
      (node (ref "L1") (pin "2") (pinfunction "2_2") (pintype "passive"))
      (node (ref "Q4") (pin "3") (pinfunction "D_3") (pintype "passive"))
      (node (ref "U$1") (pin "6") (pinfunction "VIN_6") (pintype "input"))
    )
    (net (code "42") (name "Net-(Q4-G)") (class "Default")
      (node (ref "Q4") (pin "1") (pinfunction "G_1") (pintype "passive"))
      (node (ref "R16") (pin "2") (pinfunction "2_2") (pintype "passive"))
      (node (ref "T1") (pin "3") (pinfunction "C_3") (pintype "passive"))
    )
    (net (code "43") (name "Net-(Q5-1)") (class "Default")
      (node (ref "C30") (pin "2") (pinfunction "2_2") (pintype "passive"))
      (node (ref "Q5") (pin "P$1") (pinfunction "1_P$1") (pintype "passive"))
      (node (ref "U5") (pin "8") (pinfunction "PB7(XTAL2/TOSC2)_8") (pintype "bidirectional"))
    )
    (net (code "44") (name "Net-(Q5-2)") (class "Default")
      (node (ref "C29") (pin "2") (pinfunction "2_2") (pintype "passive"))
      (node (ref "Q5") (pin "P$2") (pinfunction "2_P$2") (pintype "passive"))
      (node (ref "U5") (pin "7") (pinfunction "PB6(XTAL1/TOSC1)_7") (pintype "bidirectional"))
    )
    (net (code "45") (name "Net-(T1-B)") (class "Default")
      (node (ref "R7") (pin "1") (pinfunction "1_1") (pintype "passive"))
      (node (ref "T1") (pin "1") (pinfunction "B_1") (pintype "passive"))
    )
    (net (code "46") (name "Net-(T2-B)") (class "Default")
      (node (ref "R17") (pin "1") (pinfunction "1_1") (pintype "passive"))
      (node (ref "T2") (pin "1") (pinfunction "B_1") (pintype "passive"))
    )
    (net (code "47") (name "Net-(U$1-SW)") (class "Default")
      (node (ref "D1") (pin "A") (pinfunction "A_A") (pintype "passive"))
      (node (ref "L1") (pin "1") (pinfunction "1_1") (pintype "passive"))
      (node (ref "U$1") (pin "7") (pinfunction "SW_7") (pintype "input"))
    )
    (net (code "48") (name "Net-(U$1-VC)") (class "Default")
      (node (ref "R6") (pin "2") (pinfunction "2_2") (pintype "passive"))
      (node (ref "U$1") (pin "2") (pinfunction "VC_2") (pintype "passive"))
    )
    (net (code "49") (name "Net-(U$2-DIN)") (class "Default")
      (node (ref "R14") (pin "2") (pinfunction "2_2") (pintype "passive"))
      (node (ref "U$2") (pin "3") (pinfunction "DIN_3") (pintype "input"))
    )
    (net (code "50") (name "Net-(U$2-DIO3)") (class "Default")
      (node (ref "SJ1") (pin "1") (pinfunction "1_1") (pintype "passive"))
      (node (ref "U$2") (pin "17") (pinfunction "DIO3_17") (pintype "bidirectional"))
    )
    (net (code "51") (name "Net-(U$2-DOUT)") (class "Default")
      (node (ref "R9") (pin "2") (pinfunction "2_2") (pintype "passive"))
      (node (ref "U$2") (pin "2") (pinfunction "DOUT_2") (pintype "output"))
    )
    (net (code "52") (name "Net-(U$2-RSSI)") (class "Default")
      (node (ref "LED4") (pin "A") (pinfunction "A_A") (pintype "passive"))
      (node (ref "U$2") (pin "6") (pinfunction "RSSI_6") (pintype "bidirectional"))
    )
    (net (code "53") (name "Net-(U$3-T+)") (class "Default")
      (node (ref "JP9") (pin "1") (pinfunction "1_1") (pintype "passive"))
      (node (ref "U$3") (pin "3") (pinfunction "T+_3") (pintype "bidirectional"))
    )
    (net (code "54") (name "Net-(U1-BP)") (class "Default")
      (node (ref "C4") (pin "1") (pinfunction "1_1") (pintype "passive"))
      (node (ref "U1") (pin "4") (pinfunction "BP_4") (pintype "input"))
    )
    (net (code "55") (name "Net-(U2-CH)") (class "Default")
      (node (ref "LED1") (pin "C") (pinfunction "C_C") (pintype "passive"))
      (node (ref "U2") (pin "7") (pinfunction "CH_7") (pintype "bidirectional"))
    )
    (net (code "56") (name "Net-(U2-ISET)") (class "Default")
      (node (ref "R15") (pin "1") (pinfunction "1_1") (pintype "passive"))
      (node (ref "U2") (pin "2") (pinfunction "ISET_2") (pintype "bidirectional"))
    )
    (net (code "57") (name "Net-(U2-OK)") (class "Default")
      (node (ref "LED2") (pin "C") (pinfunction "C_C") (pintype "passive"))
      (node (ref "U2") (pin "6") (pinfunction "OK_6") (pintype "bidirectional"))
    )
    (net (code "58") (name "Net-(U2-VIN)") (class "Default")
      (node (ref "C14") (pin "+") (pinfunction "+_+") (pintype "passive"))
      (node (ref "C15") (pin "1") (pinfunction "1_1") (pintype "passive"))
      (node (ref "JP10") (pin "2") (pinfunction "2_2") (pintype "passive"))
      (node (ref "R5") (pin "2") (pinfunction "2_2") (pintype "passive"))
      (node (ref "U2") (pin "4") (pinfunction "VIN_4") (pintype "bidirectional"))
    )
    (net (code "59") (name "Net-(U3-BP)") (class "Default")
      (node (ref "C19") (pin "1") (pinfunction "1_1") (pintype "passive"))
      (node (ref "U3") (pin "4") (pinfunction "BP_4") (pintype "input"))
    )
    (net (code "60") (name "Net-(U5-AREF)") (class "Default")
      (node (ref "C28") (pin "2") (pinfunction "2_2") (pintype "passive"))
      (node (ref "U5") (pin "20") (pinfunction "AREF_20") (pintype "bidirectional"))
    )
    (net (code "61") (name "V+") (class "Default")
      (node (ref "C5") (pin "1") (pinfunction "1_1") (pintype "passive"))
      (node (ref "JP1") (pin "1") (pinfunction "1_1") (pintype "passive"))
      (node (ref "JP2") (pin "2") (pinfunction "2_2") (pintype "passive"))
      (node (ref "Q6") (pin "2") (pinfunction "S_2") (pintype "passive"))
      (node (ref "R11") (pin "2") (pinfunction "2_2") (pintype "passive"))
      (node (ref "U2") (pin "5") (pinfunction "BAT_5") (pintype "bidirectional"))
      (node (ref "U2") (pin "8") (pinfunction "FB_8") (pintype "bidirectional"))
    )
    (net (code "62") (name "unconnected-(U$1-IT-Pad5)") (class "Default")
      (node (ref "U$1") (pin "5") (pinfunction "IT_5") (pintype "input"))
    )
    (net (code "63") (name "unconnected-(U$2-CTS-Pad12)") (class "Default")
      (node (ref "U$2") (pin "12") (pinfunction "CTS_12") (pintype "output"))
    )
    (net (code "64") (name "unconnected-(U$2-DIO0-Pad20)") (class "Default")
      (node (ref "U$2") (pin "20") (pinfunction "DIO0_20") (pintype "bidirectional"))
    )
    (net (code "65") (name "unconnected-(U$2-DIO1-Pad19)") (class "Default")
      (node (ref "U$2") (pin "19") (pinfunction "DIO1_19") (pintype "bidirectional"))
    )
    (net (code "66") (name "unconnected-(U$2-DIO2-Pad18)") (class "Default")
      (node (ref "U$2") (pin "18") (pinfunction "DIO2_18") (pintype "bidirectional"))
    )
    (net (code "67") (name "unconnected-(U$2-DIO4-Pad11)") (class "Default")
      (node (ref "U$2") (pin "11") (pinfunction "DIO4_11") (pintype "bidirectional"))
    )
    (net (code "68") (name "unconnected-(U$2-DIO5-Pad15)") (class "Default")
      (node (ref "U$2") (pin "15") (pinfunction "DIO5_15") (pintype "bidirectional"))
    )
    (net (code "69") (name "unconnected-(U$2-DIO9-Pad13)") (class "Default")
      (node (ref "U$2") (pin "13") (pinfunction "DIO9_13") (pintype "bidirectional"))
    )
    (net (code "70") (name "unconnected-(U$2-DIO11-Pad7)") (class "Default")
      (node (ref "U$2") (pin "7") (pinfunction "DIO11_7") (pintype "bidirectional"))
    )
    (net (code "71") (name "unconnected-(U$2-DIO12-Pad4)") (class "Default")
      (node (ref "U$2") (pin "4") (pinfunction "DIO12_4") (pintype "bidirectional"))
    )
    (net (code "72") (name "unconnected-(U$2-RES-Pad8)") (class "Default")
      (node (ref "U$2") (pin "8") (pinfunction "RES_8") (pintype "bidirectional"))
    )
    (net (code "73") (name "unconnected-(U$2-RES-Pad14)") (class "Default")
      (node (ref "U$2") (pin "14") (pinfunction "RES_14") (pintype "bidirectional"))
    )
    (net (code "74") (name "unconnected-(U$2-RESET-Pad5)") (class "Default")
      (node (ref "U$2") (pin "5") (pinfunction "RESET_5") (pintype "input"))
    )
    (net (code "75") (name "unconnected-(U$2-RTS-Pad16)") (class "Default")
      (node (ref "U$2") (pin "16") (pinfunction "RTS_16") (pintype "input"))
    )
    (net (code "76") (name "unconnected-(U6-NC-Pad1)") (class "Default")
      (node (ref "U6") (pin "1") (pinfunction "NC_1") (pintype "bidirectional"))
    )
    (net (code "77") (name "unconnected-(U6-RSV-Pad8)") (class "Default")
      (node (ref "U6") (pin "8") (pinfunction "RSV_8") (pintype "bidirectional"))
    )
    (net (code "78") (name "unconnected-(U6-SHIELD-PadCD1)") (class "Default")
      (node (ref "U6") (pin "CD1") (pinfunction "SHIELD_CD1") (pintype "bidirectional"))
    )
    (net (code "79") (name "unconnected-(U6-SHIELD-PadCD2)") (class "Default")
      (node (ref "U6") (pin "CD2") (pinfunction "SHIELD_CD2") (pintype "bidirectional"))
    )
  )
)
